# 02_USB2UART.net
KiCad netlist of a schematic drawn in Altium Designer
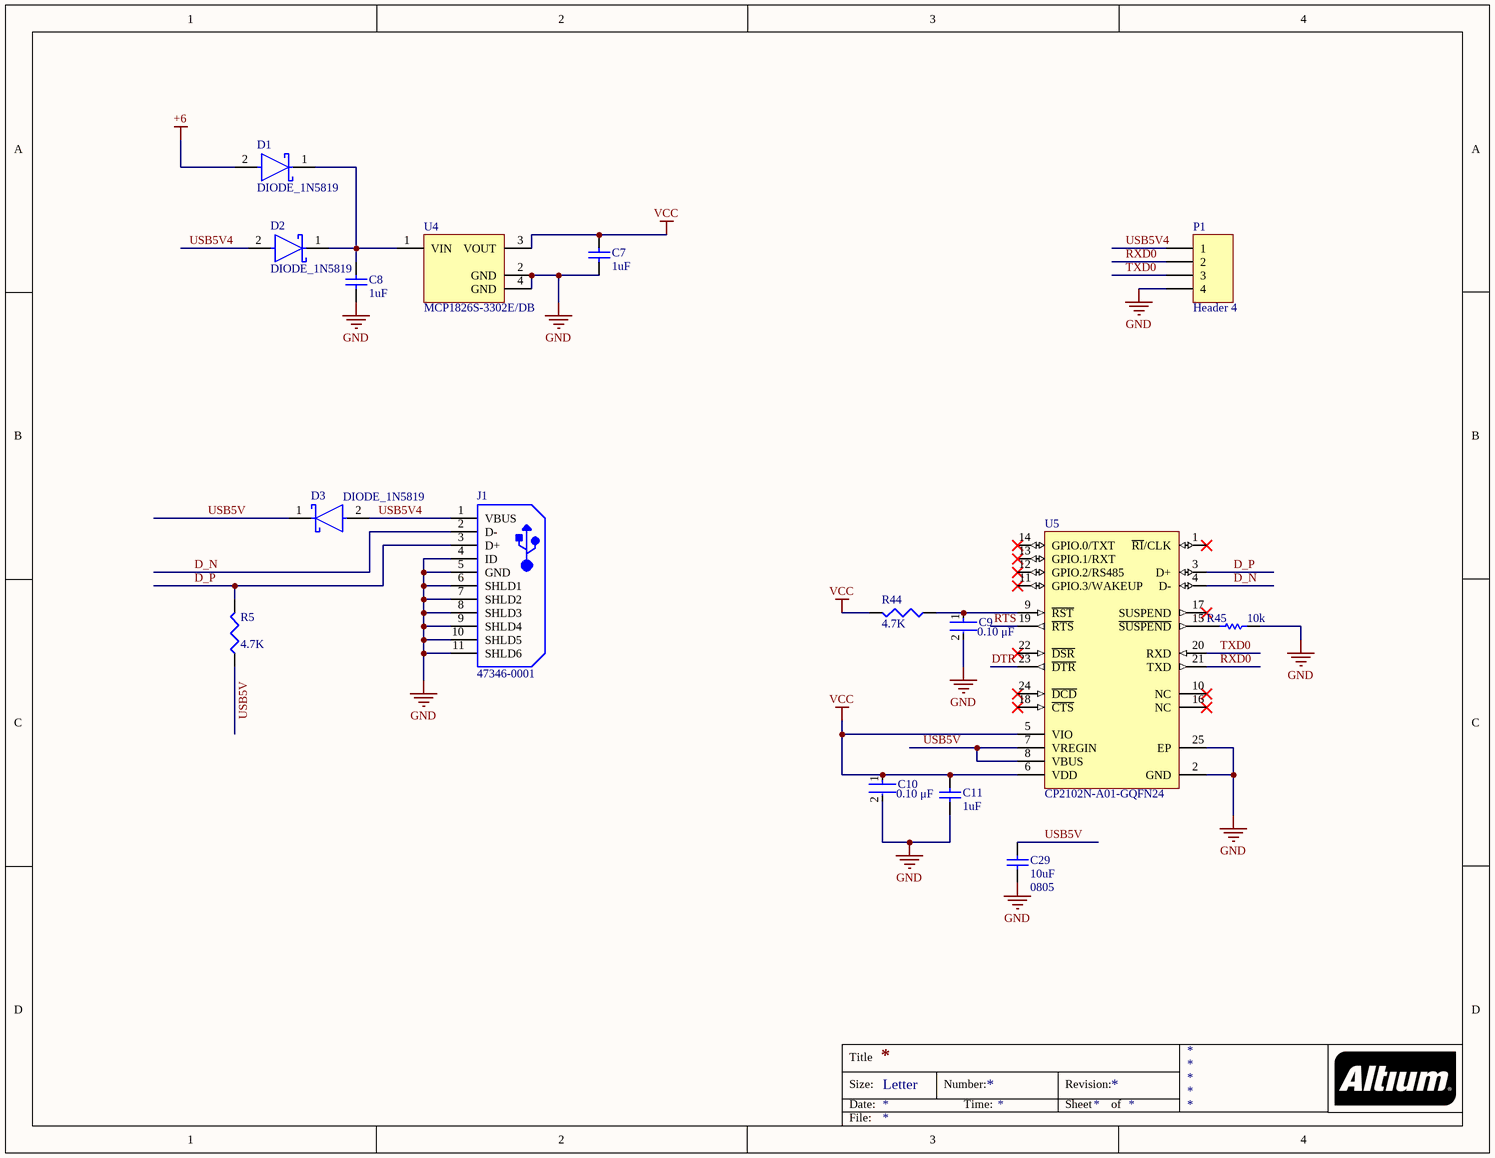
[diagram p0: 02_USB2UART.SchDoc]

(export (version "E")
  (design (tool "Eeschema 10.0.6"))
  (components
    (comp (ref "C7")
      (value "1uF")
      (footprint "CAPC1608X87X35LL15T15")
      (fields
        (field (name "MANUFACTURER") "Kemet")
        (field (name "PART NUMBER") "C0603C101J1GACTU")
        (field (name "Comment") "C0603_1UF")
      )
      (libsource (lib "Altium Content Vault") (part "CAP"))
    )
    (comp (ref "C8")
      (value "1uF")
      (footprint "CAPC1608X87X35LL15T15")
      (fields
        (field (name "MANUFACTURER") "Kemet")
        (field (name "PART NUMBER") "C0603C101J1GACTU")
        (field (name "Comment") "C0603_1UF")
      )
      (libsource (lib "Altium Content Vault") (part "CAP"))
    )
    (comp (ref "C9")
      (value "C0603_0.1UF")
      (footprint "FP-C0603C-CF-MFG")
      (description "CAP CER 0.1UF 16V X7R 0603")
      (fields
        (field (name "TOLERANCE") "0.2")
        (field (name "CAPACITANCE") "0.10 μF")
        (field (name "MANUFACTURER PART NUMBER") "C0603C104M4RAC7411")
      )
      (libsource (lib "Altium Content Vault") (part "b4654b650e69147ec39a6b967a45e02"))
    )
    (comp (ref "C10")
      (value "C0603_0.1UF")
      (footprint "FP-C0603C-CF-MFG")
      (description "CAP CER 0.1UF 16V X7R 0603")
      (fields
        (field (name "TOLERANCE") "0.2")
        (field (name "CAPACITANCE") "0.10 μF")
        (field (name "MANUFACTURER PART NUMBER") "C0603C104M4RAC7411")
      )
      (libsource (lib "Altium Content Vault") (part "b4654b650e69147ec39a6b967a45e02"))
    )
    (comp (ref "C11")
      (value "1uF")
      (footprint "CAPC1608X87X35LL15T15")
      (fields
        (field (name "MANUFACTURER") "Kemet")
        (field (name "PART NUMBER") "C0603C101J1GACTU")
        (field (name "Comment") "C0603_1UF")
      )
      (libsource (lib "Altium Content Vault") (part "CAP"))
    )
    (comp (ref "C29")
      (value "10uF")
      (footprint "CAPC2013X135X50LL10T20")
      (fields
        (field (name "MANUFACTURER") "Murata")
        (field (name "PART NUMBER") "GRM21BR61C106KE15L")
        (field (name "PACKAGE") "0805")
        (field (name "Comment") "C0805_10UF")
      )
      (libsource (lib "Altium Content Vault") (part "CAP"))
    )
    (comp (ref "D1")
      (value "DIODE_1N5819")
      (footprint "FP-SOD123-MFG")
      (description "DIODE SCHOTTKY 40V 1A SOD123")
      (fields
        (field (name "OCTOPART") "https://octopart.com/1n5819hw-7-f-diodes+inc.-323197")
        (field (name "MANUFACTURER") "Diodes Inc")
      )
      (libsource (lib "Altium Content Vault") (part "1d6ec82d83fb6aee721767c19dac4b9"))
    )
    (comp (ref "D2")
      (value "DIODE_1N5819")
      (footprint "FP-SOD123-MFG")
      (description "DIODE SCHOTTKY 40V 1A SOD123")
      (fields
        (field (name "OCTOPART") "https://octopart.com/1n5819hw-7-f-diodes+inc.-323197")
        (field (name "MANUFACTURER") "Diodes Inc")
      )
      (libsource (lib "Altium Content Vault") (part "1d6ec82d83fb6aee721767c19dac4b9"))
    )
    (comp (ref "D3")
      (value "DIODE_1N5819")
      (footprint "FP-SOD123-MFG")
      (description "DIODE SCHOTTKY 40V 1A SOD123")
      (fields
        (field (name "OCTOPART") "https://octopart.com/1n5819hw-7-f-diodes+inc.-323197")
        (field (name "MANUFACTURER") "Diodes Inc")
      )
      (libsource (lib "Altium Content Vault") (part "1d6ec82d83fb6aee721767c19dac4b9"))
    )
    (comp (ref "J1")
      (value "47346-0001")
      (footprint "MOLX-47346-0001-5_V")
      (description "Micro-USB B Receptacle with Flange, -30 to 85 degC, 5-Pin SMD, RoHS, Tape and Reel")
      (fields (field (name "MANUFACTURER") "Molex"))
      (libsource (lib "Altium Content Vault") (part "MOLX-47346-0001-5"))
    )
    (comp (ref "P1")
      (value "Header 4")
      (footprint "HDR1X4")
      (description "Header, 4-Pin")
      (fields (field (name "PUBLISHER") "Altium Limited"))
      (libsource (lib "Miscellaneous Connectors") (part "Header 4"))
    )
    (comp (ref "R5")
      (value "4.7K")
      (footprint "J1-0603")
      (description "Resistor")
      (fields (field (name "Comment") "R0603_4.7K") (field (name "PUBLISHER") "Altium Limited"))
      (libsource (lib "Miscellaneous Devices") (part "Res3"))
    )
    (comp (ref "R44")
      (value "4.7K")
      (footprint "J1-0603")
      (description "Resistor")
      (fields (field (name "Comment") "R0603_4.7K") (field (name "PUBLISHER") "Altium Limited"))
      (libsource (lib "Miscellaneous Devices") (part "Res3"))
    )
    (comp (ref "R45")
      (value "10k")
      (footprint "RESC1609X55X30LL15T15")
      (description "Chip Resistor, 10 KOhm, +/- 1%, 0.1 W, -55 to 155 degC, 0603 (1608 Metric), RoHS, Tape and Reel")
      (fields (field (name "TOLERANCE") "1%") (field (name "MANUFACTURER") "Panasonic"))
      (libsource (lib "Altium Content Vault") (part "RES-2"))
    )
    (comp (ref "U4")
      (value "MCP1826S-3302E/DB")
      (footprint "SOT-223-DB3_L")
      (description "1000 mA, Low Voltage, Low Quiescent Current LDO Regulator, 3-Pin SOT-223, Extended Temperature")
      (libsource (lib "Altium Content Vault") (part "PM-LINEREG-MCP1826-IL4"))
    )
    (comp (ref "U5")
      (value "CP2102N-A01-GQFN24")
      (footprint "SLAB-QFN-24-2550x2550TP_A_V")
      (description "USBXpress(TM) Family, 4 GPIOs, 2.2 to 3.6 V, -40 to 85 degC, 24-Pin QFN, RoHS")
      (fields (field (name "MANUFACTURER") "Silicon Labs"))
      (libsource (lib "Finger_module") (part "CMP-2000-07570-1"))
    )
  )
  (nets
    (net (code "1") (name "+6") (class "Default")
      (node (ref "D1") (pin "2") (pinfunction "A_2") (pintype "passive"))
    )
    (net (code "2") (name "/DTR") (class "Default")
      (node (ref "U5") (pin "23") (pinfunction "~{DTR}_23") (pintype "output"))
    )
    (net (code "3") (name "/D_N") (class "Default")
      (node (ref "J1") (pin "2") (pinfunction "D-_2") (pintype "passive"))
      (node (ref "U5") (pin "4") (pinfunction "D-_4") (pintype "bidirectional"))
    )
    (net (code "4") (name "/D_P") (class "Default")
      (node (ref "J1") (pin "3") (pinfunction "D+_3") (pintype "passive"))
      (node (ref "R5") (pin "2") (pinfunction "2_2") (pintype "passive"))
      (node (ref "U5") (pin "3") (pinfunction "D+_3") (pintype "bidirectional"))
    )
    (net (code "5") (name "/RTS") (class "Default")
      (node (ref "U5") (pin "19") (pinfunction "~{RTS}_19") (pintype "output"))
    )
    (net (code "6") (name "/RXD0") (class "Default")
      (node (ref "P1") (pin "2") (pinfunction "2_2") (pintype "passive"))
      (node (ref "U5") (pin "21") (pinfunction "TXD_21") (pintype "output"))
    )
    (net (code "7") (name "/TXD0") (class "Default")
      (node (ref "P1") (pin "3") (pinfunction "3_3") (pintype "passive"))
      (node (ref "U5") (pin "20") (pinfunction "RXD_20") (pintype "input"))
    )
    (net (code "8") (name "/USB5V") (class "Default")
      (node (ref "C29") (pin "2") (pinfunction "2_2") (pintype "passive"))
      (node (ref "D3") (pin "1") (pinfunction "C_1") (pintype "passive"))
      (node (ref "R5") (pin "1") (pinfunction "1_1") (pintype "passive"))
      (node (ref "U5") (pin "7") (pinfunction "VREGIN_7") (pintype "power_in"))
      (node (ref "U5") (pin "8") (pinfunction "VBUS_8") (pintype "power_in"))
    )
    (net (code "9") (name "/USB5V4") (class "Default")
      (node (ref "D2") (pin "2") (pinfunction "A_2") (pintype "passive"))
      (node (ref "D3") (pin "2") (pinfunction "A_2") (pintype "passive"))
      (node (ref "J1") (pin "1") (pinfunction "VBUS_1") (pintype "passive"))
      (node (ref "P1") (pin "1") (pinfunction "1_1") (pintype "passive"))
    )
    (net (code "10") (name "GND") (class "Default")
      (node (ref "C10") (pin "2") (pinfunction "2_2") (pintype "passive"))
      (node (ref "C11") (pin "1") (pinfunction "1_1") (pintype "passive"))
      (node (ref "C29") (pin "1") (pinfunction "1_1") (pintype "passive"))
      (node (ref "C7") (pin "1") (pinfunction "1_1") (pintype "passive"))
      (node (ref "C8") (pin "1") (pinfunction "1_1") (pintype "passive"))
      (node (ref "C9") (pin "2") (pinfunction "2_2") (pintype "passive"))
      (node (ref "J1") (pin "10") (pinfunction "SHLD5_10") (pintype "passive"))
      (node (ref "J1") (pin "11") (pinfunction "SHLD6_11") (pintype "passive"))
      (node (ref "J1") (pin "4") (pinfunction "ID_4") (pintype "passive"))
      (node (ref "J1") (pin "5") (pinfunction "GND_5") (pintype "passive"))
      (node (ref "J1") (pin "6") (pinfunction "SHLD1_6") (pintype "passive"))
      (node (ref "J1") (pin "7") (pinfunction "SHLD2_7") (pintype "passive"))
      (node (ref "J1") (pin "8") (pinfunction "SHLD3_8") (pintype "passive"))
      (node (ref "J1") (pin "9") (pinfunction "SHLD4_9") (pintype "passive"))
      (node (ref "P1") (pin "4") (pinfunction "4_4") (pintype "passive"))
      (node (ref "R45") (pin "2") (pinfunction "2_2") (pintype "passive"))
      (node (ref "U4") (pin "2") (pinfunction "GND_2") (pintype "power_in"))
      (node (ref "U4") (pin "4") (pinfunction "GND_4") (pintype "power_in"))
      (node (ref "U5") (pin "2") (pinfunction "GND_2") (pintype "power_in"))
      (node (ref "U5") (pin "25") (pinfunction "EP_25") (pintype "power_in"))
    )
    (net (code "11") (name "Net-(D1-C)") (class "Default")
      (node (ref "C8") (pin "2") (pinfunction "2_2") (pintype "passive"))
      (node (ref "D1") (pin "1") (pinfunction "C_1") (pintype "passive"))
      (node (ref "D2") (pin "1") (pinfunction "C_1") (pintype "passive"))
      (node (ref "U4") (pin "1") (pinfunction "VIN_1") (pintype "power_in"))
    )
    (net (code "12") (name "Net-(U5-~{RST})") (class "Default")
      (node (ref "C9") (pin "1") (pinfunction "1_1") (pintype "passive"))
      (node (ref "R44") (pin "1") (pinfunction "1_1") (pintype "passive"))
      (node (ref "U5") (pin "9") (pinfunction "~{RST}_9") (pintype "input"))
    )
    (net (code "13") (name "Net-(U5-~{SUSPEND})") (class "Default")
      (node (ref "R45") (pin "1") (pinfunction "1_1") (pintype "passive"))
      (node (ref "U5") (pin "15") (pinfunction "~{SUSPEND}_15") (pintype "output"))
    )
    (net (code "14") (name "VCC") (class "Default")
      (node (ref "C10") (pin "1") (pinfunction "1_1") (pintype "passive"))
      (node (ref "C11") (pin "2") (pinfunction "2_2") (pintype "passive"))
      (node (ref "C7") (pin "2") (pinfunction "2_2") (pintype "passive"))
      (node (ref "R44") (pin "2") (pinfunction "2_2") (pintype "passive"))
      (node (ref "U4") (pin "3") (pinfunction "VOUT_3") (pintype "power_in"))
      (node (ref "U5") (pin "5") (pinfunction "VIO_5") (pintype "power_in"))
      (node (ref "U5") (pin "6") (pinfunction "VDD_6") (pintype "power_in"))
    )
    (net (code "15") (name "unconnected-(U5-GPIO.0{slash}TXT-Pad14)") (class "Default")
      (node (ref "U5") (pin "14") (pinfunction "GPIO.0/TXT_14") (pintype "bidirectional+no_connect"))
    )
    (net (code "16") (name "unconnected-(U5-GPIO.1{slash}RXT-Pad13)") (class "Default")
      (node (ref "U5") (pin "13") (pinfunction "GPIO.1/RXT_13") (pintype "bidirectional+no_connect"))
    )
    (net (code "17") (name "unconnected-(U5-GPIO.2{slash}RS485-Pad12)") (class "Default")
      (node (ref "U5") (pin "12") (pinfunction "GPIO.2/RS485_12") (pintype "bidirectional+no_connect"))
    )
    (net (code "18") (name "unconnected-(U5-GPIO.3{slash}WAKEUP-Pad11)") (class "Default")
      (node (ref "U5") (pin "11") (pinfunction "GPIO.3/WAKEUP_11") (pintype "bidirectional+no_connect"))
    )
    (net (code "19") (name "unconnected-(U5-NC-Pad10)") (class "Default")
      (node (ref "U5") (pin "10") (pinfunction "NC_10") (pintype "passive+no_connect"))
    )
    (net (code "20") (name "unconnected-(U5-NC-Pad16)") (class "Default")
      (node (ref "U5") (pin "16") (pinfunction "NC_16") (pintype "passive+no_connect"))
    )
    (net (code "21") (name "unconnected-(U5-SUSPEND-Pad17)") (class "Default")
      (node (ref "U5") (pin "17") (pinfunction "SUSPEND_17") (pintype "output+no_connect"))
    )
    (net (code "22") (name "unconnected-(U5-~{CTS}-Pad18)") (class "Default")
      (node (ref "U5") (pin "18") (pinfunction "~{CTS}_18") (pintype "input+no_connect"))
    )
    (net (code "23") (name "unconnected-(U5-~{DCD}-Pad24)") (class "Default")
      (node (ref "U5") (pin "24") (pinfunction "~{DCD}_24") (pintype "input+no_connect"))
    )
    (net (code "24") (name "unconnected-(U5-~{DSR}-Pad22)") (class "Default")
      (node (ref "U5") (pin "22") (pinfunction "~{DSR}_22") (pintype "input+no_connect"))
    )
    (net (code "25") (name "unconnected-(U5-~{RI}{slash}CLK-Pad1)") (class "Default")
      (node (ref "U5") (pin "1") (pinfunction "~{RI}/CLK_1") (pintype "bidirectional+no_connect"))
    )
  )
)
